# T08-TxClicker-Rev1a.net
KiCad netlist of a schematic drawn in EAGLE
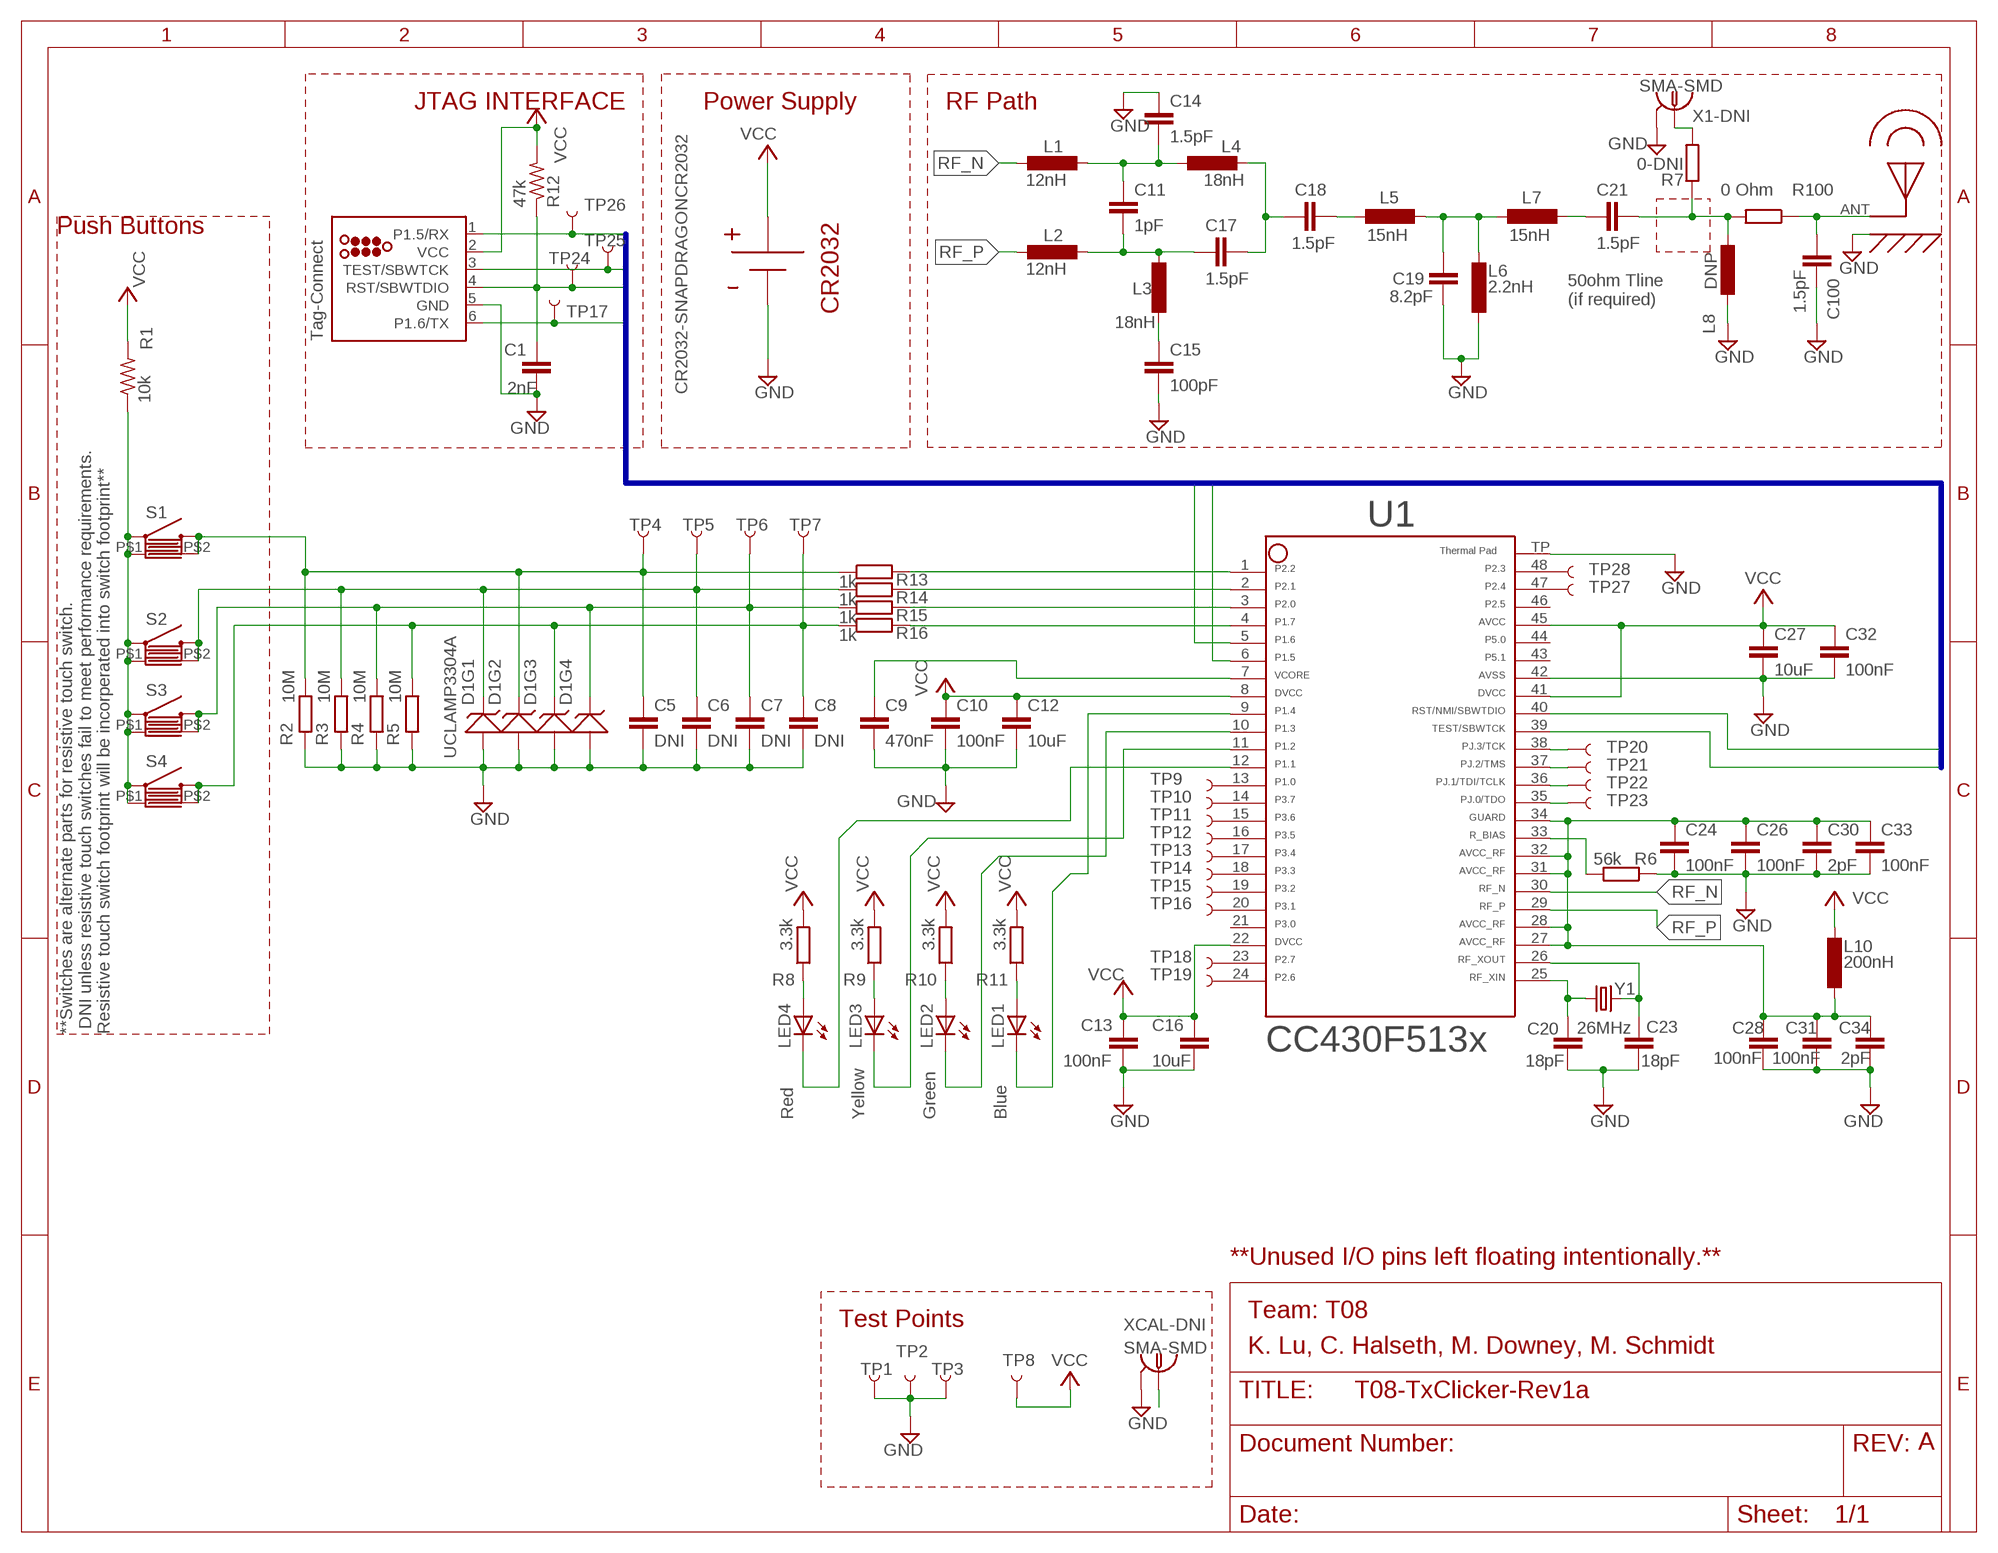
[diagram p0: schematic, sheet 1]

(export (version "E")
  (design (tool "Eeschema 10.0.6"))
  (components
    (comp (ref "C1")
      (value "2nF")
      (footprint "eagle-import:C0603")
      (libsource (lib "eagle-import") (part "C0603"))
    )
    (comp (ref "C5")
      (value "DNI")
      (footprint "eagle-import:C0603")
      (libsource (lib "eagle-import") (part "C0603"))
    )
    (comp (ref "C6")
      (value "DNI")
      (footprint "eagle-import:C0603")
      (libsource (lib "eagle-import") (part "C0603"))
    )
    (comp (ref "C7")
      (value "DNI")
      (footprint "eagle-import:C0603")
      (libsource (lib "eagle-import") (part "C0603"))
    )
    (comp (ref "C8")
      (value "DNI")
      (footprint "eagle-import:C0603")
      (libsource (lib "eagle-import") (part "C0603"))
    )
    (comp (ref "C9")
      (value "470nF")
      (footprint "eagle-import:C0603")
      (libsource (lib "eagle-import") (part "C0603"))
    )
    (comp (ref "C10")
      (value "100nF")
      (footprint "eagle-import:C0603")
      (libsource (lib "eagle-import") (part "C0603"))
    )
    (comp (ref "C11")
      (value "1pF")
      (footprint "eagle-import:C0402")
      (libsource (lib "eagle-import") (part "C0402"))
    )
    (comp (ref "C12")
      (value "10uF")
      (footprint "eagle-import:C0603")
      (libsource (lib "eagle-import") (part "C0603"))
    )
    (comp (ref "C13")
      (value "100nF")
      (footprint "eagle-import:C0603")
      (libsource (lib "eagle-import") (part "C0603"))
    )
    (comp (ref "C14")
      (value "1.5pF")
      (footprint "eagle-import:C0402")
      (libsource (lib "eagle-import") (part "C0402"))
    )
    (comp (ref "C15")
      (value "100pF")
      (footprint "eagle-import:C0402")
      (libsource (lib "eagle-import") (part "C0402"))
    )
    (comp (ref "C16")
      (value "10uF")
      (footprint "eagle-import:C0603")
      (libsource (lib "eagle-import") (part "C0603"))
    )
    (comp (ref "C17")
      (value "1.5pF")
      (footprint "eagle-import:C0402")
      (libsource (lib "eagle-import") (part "C0402"))
    )
    (comp (ref "C18")
      (value "1.5pF")
      (footprint "eagle-import:C0402")
      (libsource (lib "eagle-import") (part "C0402"))
    )
    (comp (ref "C19")
      (value "8.2pF")
      (footprint "eagle-import:C0402")
      (libsource (lib "eagle-import") (part "C0402"))
    )
    (comp (ref "C20")
      (value "18pF")
      (footprint "eagle-import:C0603")
      (libsource (lib "eagle-import") (part "C0603"))
    )
    (comp (ref "C21")
      (value "1.5pF")
      (footprint "eagle-import:C0402")
      (libsource (lib "eagle-import") (part "C0402"))
    )
    (comp (ref "C23")
      (value "18pF")
      (footprint "eagle-import:C0603")
      (libsource (lib "eagle-import") (part "C0603"))
    )
    (comp (ref "C24")
      (value "100nF")
      (footprint "eagle-import:C0603")
      (libsource (lib "eagle-import") (part "C0603"))
    )
    (comp (ref "C26")
      (value "100nF")
      (footprint "eagle-import:C0603")
      (libsource (lib "eagle-import") (part "C0603"))
    )
    (comp (ref "C27")
      (value "10uF")
      (footprint "eagle-import:C0603")
      (libsource (lib "eagle-import") (part "C0603"))
    )
    (comp (ref "C28")
      (value "100nF")
      (footprint "eagle-import:C0603")
      (libsource (lib "eagle-import") (part "C0603"))
    )
    (comp (ref "C30")
      (value "2pF")
      (footprint "eagle-import:C0603")
      (libsource (lib "eagle-import") (part "C0603"))
    )
    (comp (ref "C31")
      (value "100nF")
      (footprint "eagle-import:C0603")
      (libsource (lib "eagle-import") (part "C0603"))
    )
    (comp (ref "C32")
      (value "100nF")
      (footprint "eagle-import:C0603")
      (libsource (lib "eagle-import") (part "C0603"))
    )
    (comp (ref "C33")
      (value "100nF")
      (footprint "eagle-import:C0603")
      (libsource (lib "eagle-import") (part "C0603"))
    )
    (comp (ref "C34")
      (value "2pF")
      (footprint "eagle-import:C0603")
      (libsource (lib "eagle-import") (part "C0603"))
    )
    (comp (ref "C100")
      (value "1.5pF")
      (footprint "eagle-import:C0402")
      (libsource (lib "eagle-import") (part "C0402"))
    )
    (comp (ref "D1")
      (value "UCLAMP3304A")
      (footprint "eagle-import:SOT666")
      (libsource (lib "eagle-import") (part "UCLAMP3304A"))
    )
    (comp (ref "L1")
      (value "12nH")
      (footprint "eagle-import:L0402")
      (libsource (lib "eagle-import") (part "LL0402"))
    )
    (comp (ref "L2")
      (value "12nH")
      (footprint "eagle-import:L0402")
      (libsource (lib "eagle-import") (part "LL0402"))
    )
    (comp (ref "L3")
      (value "18nH")
      (footprint "eagle-import:L0402")
      (libsource (lib "eagle-import") (part "LL0402"))
    )
    (comp (ref "L4")
      (value "18nH")
      (footprint "eagle-import:L0402")
      (libsource (lib "eagle-import") (part "LL0402"))
    )
    (comp (ref "L5")
      (value "15nH")
      (footprint "eagle-import:L0402")
      (libsource (lib "eagle-import") (part "LL0402"))
    )
    (comp (ref "L6")
      (value "2.2nH")
      (footprint "eagle-import:L0402")
      (libsource (lib "eagle-import") (part "LL0402"))
    )
    (comp (ref "L7")
      (value "15nH")
      (footprint "eagle-import:L0402")
      (libsource (lib "eagle-import") (part "LL0402"))
    )
    (comp (ref "L8")
      (value "DNP")
      (footprint "eagle-import:L0402")
      (libsource (lib "eagle-import") (part "LL0402"))
    )
    (comp (ref "L10")
      (value "200nH")
      (footprint "eagle-import:L0603")
      (libsource (lib "eagle-import") (part "LL0603"))
    )
    (comp (ref "LED1")
      (value "Blue")
      (footprint "eagle-import:CHIP-LED0603")
      (libsource (lib "eagle-import") (part "LEDCHIP-LED0603"))
    )
    (comp (ref "LED2")
      (value "Green")
      (footprint "eagle-import:CHIP-LED0603")
      (libsource (lib "eagle-import") (part "LEDCHIP-LED0603"))
    )
    (comp (ref "LED3")
      (value "Yellow")
      (footprint "eagle-import:CHIP-LED0603")
      (libsource (lib "eagle-import") (part "LEDCHIP-LED0603"))
    )
    (comp (ref "LED4")
      (value "Red")
      (footprint "eagle-import:CHIP-LED0603")
      (libsource (lib "eagle-import") (part "LEDCHIP-LED0603"))
    )
    (comp (ref "R1")
      (value "10k")
      (footprint "eagle-import:R0603")
      (libsource (lib "eagle-import") (part "R-US_R0603"))
    )
    (comp (ref "R2")
      (value "10M")
      (footprint "eagle-import:R0603")
      (libsource (lib "eagle-import") (part "R0603"))
    )
    (comp (ref "R3")
      (value "10M")
      (footprint "eagle-import:R0603")
      (libsource (lib "eagle-import") (part "R0603"))
    )
    (comp (ref "R4")
      (value "10M")
      (footprint "eagle-import:R0603")
      (libsource (lib "eagle-import") (part "R0603"))
    )
    (comp (ref "R5")
      (value "10M")
      (footprint "eagle-import:R0603")
      (libsource (lib "eagle-import") (part "R0603"))
    )
    (comp (ref "R6")
      (value "56k")
      (footprint "eagle-import:R0603")
      (libsource (lib "eagle-import") (part "R0603"))
    )
    (comp (ref "R7")
      (value "0-DNI")
      (footprint "eagle-import:R0603")
      (libsource (lib "eagle-import") (part "R0603"))
    )
    (comp (ref "R8")
      (value "3.3k")
      (footprint "eagle-import:R0603")
      (libsource (lib "eagle-import") (part "R0603"))
    )
    (comp (ref "R9")
      (value "3.3k")
      (footprint "eagle-import:R0603")
      (libsource (lib "eagle-import") (part "R0603"))
    )
    (comp (ref "R10")
      (value "3.3k")
      (footprint "eagle-import:R0603")
      (libsource (lib "eagle-import") (part "R0603"))
    )
    (comp (ref "R11")
      (value "3.3k")
      (footprint "eagle-import:R0603")
      (libsource (lib "eagle-import") (part "R0603"))
    )
    (comp (ref "R12")
      (value "47k")
      (footprint "eagle-import:R0603")
      (libsource (lib "eagle-import") (part "R-US_R0603"))
    )
    (comp (ref "R13")
      (value "1k")
      (footprint "eagle-import:R0603")
      (libsource (lib "eagle-import") (part "R0603"))
    )
    (comp (ref "R14")
      (value "1k")
      (footprint "eagle-import:R0603")
      (libsource (lib "eagle-import") (part "R0603"))
    )
    (comp (ref "R15")
      (value "1k")
      (footprint "eagle-import:R0603")
      (libsource (lib "eagle-import") (part "R0603"))
    )
    (comp (ref "R16")
      (value "1k")
      (footprint "eagle-import:R0603")
      (libsource (lib "eagle-import") (part "R0603"))
    )
    (comp (ref "R100")
      (value "0 Ohm")
      (footprint "eagle-import:R0402")
      (libsource (lib "eagle-import") (part "R0402"))
    )
    (comp (ref "S1")
      (value "TOUCHPAD_SWITCH_COMBOSWITC_TOUCHPAD")
      (footprint "eagle-import:TACTILE-PTH-12MM")
      (libsource (lib "eagle-import") (part "TOUCHPAD_SWITCH_COMBOSWITC_TOUCHPAD"))
    )
    (comp (ref "S2")
      (value "TOUCHPAD_SWITCH_COMBOSWITC_TOUCHPAD")
      (footprint "eagle-import:TACTILE-PTH-12MM")
      (libsource (lib "eagle-import") (part "TOUCHPAD_SWITCH_COMBOSWITC_TOUCHPAD"))
    )
    (comp (ref "S3")
      (value "TOUCHPAD_SWITCH_COMBOSWITC_TOUCHPAD")
      (footprint "eagle-import:TACTILE-PTH-12MM")
      (libsource (lib "eagle-import") (part "TOUCHPAD_SWITCH_COMBOSWITC_TOUCHPAD"))
    )
    (comp (ref "S4")
      (value "TOUCHPAD_SWITCH_COMBOSWITC_TOUCHPAD")
      (footprint "eagle-import:TACTILE-PTH-12MM")
      (libsource (lib "eagle-import") (part "TOUCHPAD_SWITCH_COMBOSWITC_TOUCHPAD"))
    )
    (comp (ref "TP1")
      (value "TEST-POINT3")
      (footprint "eagle-import:PAD.03X.03")
      (libsource (lib "eagle-import") (part "TEST-POINT3"))
    )
    (comp (ref "TP2")
      (value "TEST-POINT3")
      (footprint "eagle-import:PAD.03X.03")
      (libsource (lib "eagle-import") (part "TEST-POINT3"))
    )
    (comp (ref "TP3")
      (value "TEST-POINT3")
      (footprint "eagle-import:PAD.03X.03")
      (libsource (lib "eagle-import") (part "TEST-POINT3"))
    )
    (comp (ref "TP4")
      (value "TEST-POINT3")
      (footprint "eagle-import:PAD.03X.03")
      (libsource (lib "eagle-import") (part "TEST-POINT3"))
    )
    (comp (ref "TP5")
      (value "TEST-POINT3")
      (footprint "eagle-import:PAD.03X.03")
      (libsource (lib "eagle-import") (part "TEST-POINT3"))
    )
    (comp (ref "TP6")
      (value "TEST-POINT3")
      (footprint "eagle-import:PAD.03X.03")
      (libsource (lib "eagle-import") (part "TEST-POINT3"))
    )
    (comp (ref "TP7")
      (value "TEST-POINT3")
      (footprint "eagle-import:PAD.03X.03")
      (libsource (lib "eagle-import") (part "TEST-POINT3"))
    )
    (comp (ref "TP8")
      (value "TEST-POINT3")
      (footprint "eagle-import:PAD.03X.03")
      (libsource (lib "eagle-import") (part "TEST-POINT3"))
    )
    (comp (ref "TP9")
      (value "TP9")
      (footprint "eagle-import:PAD.03X.03")
      (libsource (lib "eagle-import") (part "TEST-POINT3"))
    )
    (comp (ref "TP10")
      (value "TEST-POINT3")
      (footprint "eagle-import:PAD.03X.03")
      (libsource (lib "eagle-import") (part "TEST-POINT3"))
    )
    (comp (ref "TP11")
      (value "TEST-POINT3")
      (footprint "eagle-import:PAD.03X.03")
      (libsource (lib "eagle-import") (part "TEST-POINT3"))
    )
    (comp (ref "TP12")
      (value "TEST-POINT3")
      (footprint "eagle-import:PAD.03X.03")
      (libsource (lib "eagle-import") (part "TEST-POINT3"))
    )
    (comp (ref "TP13")
      (value "TEST-POINT3")
      (footprint "eagle-import:PAD.03X.03")
      (libsource (lib "eagle-import") (part "TEST-POINT3"))
    )
    (comp (ref "TP14")
      (value "TEST-POINT3")
      (footprint "eagle-import:PAD.03X.03")
      (libsource (lib "eagle-import") (part "TEST-POINT3"))
    )
    (comp (ref "TP15")
      (value "TEST-POINT3")
      (footprint "eagle-import:PAD.03X.03")
      (libsource (lib "eagle-import") (part "TEST-POINT3"))
    )
    (comp (ref "TP16")
      (value "TEST-POINT3")
      (footprint "eagle-import:PAD.03X.03")
      (libsource (lib "eagle-import") (part "TEST-POINT3"))
    )
    (comp (ref "TP17")
      (value "TEST-POINT3")
      (footprint "eagle-import:PAD.03X.03")
      (libsource (lib "eagle-import") (part "TEST-POINT3"))
    )
    (comp (ref "TP18")
      (value "TEST-POINT3")
      (footprint "eagle-import:PAD.03X.03")
      (libsource (lib "eagle-import") (part "TEST-POINT3"))
    )
    (comp (ref "TP19")
      (value "TEST-POINT3")
      (footprint "eagle-import:PAD.03X.03")
      (libsource (lib "eagle-import") (part "TEST-POINT3"))
    )
    (comp (ref "TP20")
      (value "TEST-POINT3")
      (footprint "eagle-import:PAD.03X.03")
      (libsource (lib "eagle-import") (part "TEST-POINT3"))
    )
    (comp (ref "TP21")
      (value "TEST-POINT3")
      (footprint "eagle-import:PAD.03X.03")
      (libsource (lib "eagle-import") (part "TEST-POINT3"))
    )
    (comp (ref "TP22")
      (value "TEST-POINT3")
      (footprint "eagle-import:PAD.03X.03")
      (libsource (lib "eagle-import") (part "TEST-POINT3"))
    )
    (comp (ref "TP23")
      (value "TEST-POINT3")
      (footprint "eagle-import:PAD.03X.03")
      (libsource (lib "eagle-import") (part "TEST-POINT3"))
    )
    (comp (ref "TP24")
      (value "TEST-POINT3")
      (footprint "eagle-import:PAD.03X.03")
      (libsource (lib "eagle-import") (part "TEST-POINT3"))
    )
    (comp (ref "TP25")
      (value "TEST-POINT3")
      (footprint "eagle-import:PAD.03X.03")
      (libsource (lib "eagle-import") (part "TEST-POINT3"))
    )
    (comp (ref "TP26")
      (value "TEST-POINT3")
      (footprint "eagle-import:PAD.03X.03")
      (libsource (lib "eagle-import") (part "TEST-POINT3"))
    )
    (comp (ref "TP27")
      (value "TEST-POINT3")
      (footprint "eagle-import:PAD.03X.03")
      (libsource (lib "eagle-import") (part "TEST-POINT3"))
    )
    (comp (ref "TP28")
      (value "TEST-POINT3")
      (footprint "eagle-import:PAD.03X.03")
      (libsource (lib "eagle-import") (part "TEST-POINT3"))
    )
    (comp (ref "U$1")
      (value "TC2030-MCP")
      (footprint "eagle-import:TC2030-MCP")
      (libsource (lib "eagle-import") (part "TC2030-MCP"))
    )
    (comp (ref "U$5")
      (value "CR2032-SNAPDRAGONCR2032")
      (footprint "eagle-import:CR2032-SNAPDRAGON")
      (libsource (lib "eagle-import") (part "CR2032-SNAPDRAGONCR2032"))
    )
    (comp (ref "U$6")
      (value "PCB_ANTENNA_915MHZOSHP")
      (footprint "eagle-import:PCB_ANTENNA_915MHZ")
      (libsource (lib "eagle-import") (part "PCB_ANTENNA_915MHZOSHP"))
    )
    (comp (ref "U1")
      (value "CC430F513X---RGZ48")
      (footprint "eagle-import:RGZ48")
      (libsource (lib "eagle-import") (part "CC430F513X---RGZ48"))
    )
    (comp (ref "X1-DNI")
      (value "SMA-SMD")
      (footprint "eagle-import:SMA-SMD")
      (libsource (lib "eagle-import") (part "SMA-SMD"))
    )
    (comp (ref "XCAL-DNI")
      (value "SMA-SMD")
      (footprint "eagle-import:SMA-SMD")
      (libsource (lib "eagle-import") (part "SMA-SMD"))
    )
    (comp (ref "Y1")
      (value "26MHz")
      (footprint "eagle-import:CRYSTAL-TXC-7A")
      (libsource (lib "eagle-import") (part "CRYSTALTXC-7A"))
    )
  )
  (nets
    (net (code "1") (name "/P1.5{slash}RX") (class "Default")
      (node (ref "TP26") (pin "P$1") (pinfunction "1_P$1") (pintype "bidirectional"))
      (node (ref "U$1") (pin "1") (pinfunction "P1.5/RX_1") (pintype "bidirectional"))
      (node (ref "U1") (pin "6") (pinfunction "6_6") (pintype "bidirectional"))
    )
    (net (code "2") (name "/P1.6{slash}TX") (class "Default")
      (node (ref "TP17") (pin "P$1") (pinfunction "1_P$1") (pintype "bidirectional"))
      (node (ref "U$1") (pin "6") (pinfunction "P1.6/TX_6") (pintype "bidirectional"))
      (node (ref "U1") (pin "5") (pinfunction "5_5") (pintype "bidirectional"))
    )
    (net (code "3") (name "/RST{slash}NMI{slash}SBWTDIO") (class "Default")
      (node (ref "C1") (pin "1") (pinfunction "1_1") (pintype "passive"))
      (node (ref "R12") (pin "1") (pinfunction "1_1") (pintype "passive"))
      (node (ref "TP24") (pin "P$1") (pinfunction "1_P$1") (pintype "bidirectional"))
      (node (ref "U$1") (pin "4") (pinfunction "RST/SBWTDIO_4") (pintype "bidirectional"))
      (node (ref "U1") (pin "40") (pinfunction "40_40") (pintype "bidirectional"))
    )
    (net (code "4") (name "/TEST{slash}SBWTCK") (class "Default")
      (node (ref "TP25") (pin "P$1") (pinfunction "1_P$1") (pintype "bidirectional"))
      (node (ref "U$1") (pin "3") (pinfunction "TEST/SBWTCK_3") (pintype "bidirectional"))
      (node (ref "U1") (pin "39") (pinfunction "39_39") (pintype "input"))
    )
    (net (code "5") (name "GND") (class "Default")
      (node (ref "C1") (pin "2") (pinfunction "2_2") (pintype "passive"))
      (node (ref "C10") (pin "2") (pinfunction "2_2") (pintype "passive"))
      (node (ref "C100") (pin "P$1") (pinfunction "1_P$1") (pintype "passive"))
      (node (ref "C12") (pin "2") (pinfunction "2_2") (pintype "passive"))
      (node (ref "C13") (pin "2") (pinfunction "2_2") (pintype "passive"))
      (node (ref "C14") (pin "P$1") (pinfunction "1_P$1") (pintype "passive"))
      (node (ref "C15") (pin "P$2") (pinfunction "2_P$2") (pintype "passive"))
      (node (ref "C16") (pin "2") (pinfunction "2_2") (pintype "passive"))
      (node (ref "C19") (pin "P$1") (pinfunction "1_P$1") (pintype "passive"))
      (node (ref "C20") (pin "2") (pinfunction "2_2") (pintype "passive"))
      (node (ref "C23") (pin "2") (pinfunction "2_2") (pintype "passive"))
      (node (ref "C24") (pin "2") (pinfunction "2_2") (pintype "passive"))
      (node (ref "C26") (pin "2") (pinfunction "2_2") (pintype "passive"))
      (node (ref "C27") (pin "2") (pinfunction "2_2") (pintype "passive"))
      (node (ref "C28") (pin "2") (pinfunction "2_2") (pintype "passive"))
      (node (ref "C30") (pin "2") (pinfunction "2_2") (pintype "passive"))
      (node (ref "C31") (pin "2") (pinfunction "2_2") (pintype "passive"))
      (node (ref "C32") (pin "2") (pinfunction "2_2") (pintype "passive"))
      (node (ref "C33") (pin "2") (pinfunction "2_2") (pintype "passive"))
      (node (ref "C34") (pin "2") (pinfunction "2_2") (pintype "passive"))
      (node (ref "C5") (pin "2") (pinfunction "2_2") (pintype "passive"))
      (node (ref "C6") (pin "2") (pinfunction "2_2") (pintype "passive"))
      (node (ref "C7") (pin "2") (pinfunction "2_2") (pintype "passive"))
      (node (ref "C8") (pin "2") (pinfunction "2_2") (pintype "passive"))
      (node (ref "C9") (pin "2") (pinfunction "2_2") (pintype "passive"))
      (node (ref "D1") (pin "2") (pinfunction "2_2") (pintype "bidirectional"))
      (node (ref "D1") (pin "5") (pinfunction "2_5") (pintype "bidirectional"))
      (node (ref "L6") (pin "P$2") (pinfunction "2_P$2") (pintype "passive"))
      (node (ref "L8") (pin "P$1") (pinfunction "1_P$1") (pintype "passive"))
      (node (ref "R2") (pin "1") (pinfunction "1_1") (pintype "passive"))
      (node (ref "R3") (pin "1") (pinfunction "1_1") (pintype "passive"))
      (node (ref "R4") (pin "1") (pinfunction "1_1") (pintype "passive"))
      (node (ref "R5") (pin "1") (pinfunction "1_1") (pintype "passive"))
      (node (ref "R6") (pin "1") (pinfunction "1_1") (pintype "passive"))
      (node (ref "TP1") (pin "P$1") (pinfunction "1_P$1") (pintype "bidirectional"))
      (node (ref "TP2") (pin "P$1") (pinfunction "1_P$1") (pintype "bidirectional"))
      (node (ref "TP3") (pin "P$1") (pinfunction "1_P$1") (pintype "bidirectional"))
      (node (ref "U$1") (pin "5") (pinfunction "GND_5") (pintype "power_in"))
      (node (ref "U$5") (pin "V-") (pinfunction "V-_V-") (pintype "bidirectional"))
      (node (ref "U$6") (pin "GPLANE") (pinfunction "GND_GPLANE") (pintype "power_in"))
      (node (ref "U1") (pin "42") (pinfunction "42_42") (pintype "power_in"))
      (node (ref "U1") (pin "TP") (pinfunction "49_TP") (pintype "power_in"))
      (node (ref "X1-DNI") (pin "2@1") (pinfunction "2_2@1") (pintype "passive"))
      (node (ref "X1-DNI") (pin "2@2") (pinfunction "2_2@2") (pintype "passive"))
      (node (ref "X1-DNI") (pin "2@3") (pinfunction "2_2@3") (pintype "passive"))
      (node (ref "X1-DNI") (pin "2@4") (pinfunction "2_2@4") (pintype "passive"))
      (node (ref "X1-DNI") (pin "2@5") (pinfunction "2_2@5") (pintype "passive"))
      (node (ref "X1-DNI") (pin "2@6") (pinfunction "2_2@6") (pintype "passive"))
      (node (ref "XCAL-DNI") (pin "2@1") (pinfunction "2_2@1") (pintype "passive"))
      (node (ref "XCAL-DNI") (pin "2@2") (pinfunction "2_2@2") (pintype "passive"))
      (node (ref "XCAL-DNI") (pin "2@3") (pinfunction "2_2@3") (pintype "passive"))
      (node (ref "XCAL-DNI") (pin "2@4") (pinfunction "2_2@4") (pintype "passive"))
      (node (ref "XCAL-DNI") (pin "2@5") (pinfunction "2_2@5") (pintype "passive"))
      (node (ref "XCAL-DNI") (pin "2@6") (pinfunction "2_2@6") (pintype "passive"))
    )
    (net (code "6") (name "Net-(C9-Pad1)") (class "Default")
      (node (ref "C9") (pin "1") (pinfunction "1_1") (pintype "passive"))
      (node (ref "U1") (pin "7") (pinfunction "7_7") (pintype "power_in"))
    )
    (net (code "7") (name "Net-(C11-1)") (class "Default")
      (node (ref "C11") (pin "P$1") (pinfunction "1_P$1") (pintype "passive"))
      (node (ref "C14") (pin "P$2") (pinfunction "2_P$2") (pintype "passive"))
      (node (ref "L1") (pin "P$1") (pinfunction "1_P$1") (pintype "passive"))
      (node (ref "L4") (pin "P$2") (pinfunction "2_P$2") (pintype "passive"))
    )
    (net (code "8") (name "Net-(C11-2)") (class "Default")
      (node (ref "C11") (pin "P$2") (pinfunction "2_P$2") (pintype "passive"))
      (node (ref "C17") (pin "P$2") (pinfunction "2_P$2") (pintype "passive"))
      (node (ref "L2") (pin "P$1") (pinfunction "1_P$1") (pintype "passive"))
      (node (ref "L3") (pin "P$1") (pinfunction "1_P$1") (pintype "passive"))
    )
    (net (code "9") (name "Net-(C15-1)") (class "Default")
      (node (ref "C15") (pin "P$1") (pinfunction "1_P$1") (pintype "passive"))
      (node (ref "L3") (pin "P$2") (pinfunction "2_P$2") (pintype "passive"))
    )
    (net (code "10") (name "Net-(C17-1)") (class "Default")
      (node (ref "C17") (pin "P$1") (pinfunction "1_P$1") (pintype "passive"))
      (node (ref "C18") (pin "P$1") (pinfunction "1_P$1") (pintype "passive"))
      (node (ref "L4") (pin "P$1") (pinfunction "1_P$1") (pintype "passive"))
    )
    (net (code "11") (name "Net-(C18-2)") (class "Default")
      (node (ref "C18") (pin "P$2") (pinfunction "2_P$2") (pintype "passive"))
      (node (ref "L5") (pin "P$1") (pinfunction "1_P$1") (pintype "passive"))
    )
    (net (code "12") (name "Net-(C19-2)") (class "Default")
      (node (ref "C19") (pin "P$2") (pinfunction "2_P$2") (pintype "passive"))
      (node (ref "L5") (pin "P$2") (pinfunction "2_P$2") (pintype "passive"))
      (node (ref "L6") (pin "P$1") (pinfunction "1_P$1") (pintype "passive"))
      (node (ref "L7") (pin "P$1") (pinfunction "1_P$1") (pintype "passive"))
    )
    (net (code "13") (name "Net-(C21-1)") (class "Default")
      (node (ref "C21") (pin "P$1") (pinfunction "1_P$1") (pintype "passive"))
      (node (ref "L8") (pin "P$2") (pinfunction "2_P$2") (pintype "passive"))
      (node (ref "R100") (pin "P$2") (pinfunction "2_P$2") (pintype "passive"))
      (node (ref "R7") (pin "1") (pinfunction "1_1") (pintype "passive"))
    )
    (net (code "14") (name "Net-(C21-2)") (class "Default")
      (node (ref "C21") (pin "P$2") (pinfunction "2_P$2") (pintype "passive"))
      (node (ref "L7") (pin "P$2") (pinfunction "2_P$2") (pintype "passive"))
    )
    (net (code "15") (name "Net-(C24-Pad1)") (class "Default")
      (node (ref "C24") (pin "1") (pinfunction "1_1") (pintype "passive"))
      (node (ref "C26") (pin "1") (pinfunction "1_1") (pintype "passive"))
      (node (ref "C28") (pin "1") (pinfunction "1_1") (pintype "passive"))
      (node (ref "C30") (pin "1") (pinfunction "1_1") (pintype "passive"))
      (node (ref "C31") (pin "1") (pinfunction "1_1") (pintype "passive"))
      (node (ref "C33") (pin "1") (pinfunction "1_1") (pintype "passive"))
      (node (ref "C34") (pin "1") (pinfunction "1_1") (pintype "passive"))
      (node (ref "L10") (pin "2") (pinfunction "2_2") (pintype "passive"))
      (node (ref "U1") (pin "27") (pinfunction "27_27") (pintype "power_in"))
      (node (ref "U1") (pin "28") (pinfunction "28_28") (pintype "bidirectional"))
      (node (ref "U1") (pin "31") (pinfunction "31_31") (pintype "power_in"))
      (node (ref "U1") (pin "32") (pinfunction "32_32") (pintype "power_in"))
      (node (ref "U1") (pin "34") (pinfunction "34_34") (pintype "power_in"))
    )
    (net (code "16") (name "Net-(C100-2)") (class "Default")
      (node (ref "C100") (pin "P$2") (pinfunction "2_P$2") (pintype "passive"))
      (node (ref "R100") (pin "P$1") (pinfunction "1_P$1") (pintype "passive"))
      (node (ref "U$6") (pin "ANT") (pinfunction "ANT_ANT") (pintype "input"))
    )
    (net (code "17") (name "Net-(D1B-1)") (class "Default")
      (node (ref "C5") (pin "1") (pinfunction "1_1") (pintype "passive"))
      (node (ref "D1") (pin "3") (pinfunction "1_3") (pintype "bidirectional"))
      (node (ref "R13") (pin "1") (pinfunction "1_1") (pintype "passive"))
      (node (ref "R2") (pin "2") (pinfunction "2_2") (pintype "passive"))
      (node (ref "S1") (pin "3") (pinfunction "TOP_3") (pintype "passive"))
      (node (ref "S1") (pin "P$2") (pinfunction "TOP_P$2") (pintype "passive"))
      (node (ref "TP4") (pin "P$1") (pinfunction "1_P$1") (pintype "bidirectional"))
    )
    (net (code "18") (name "Net-(D1C-P$1)") (class "Default")
      (node (ref "C8") (pin "1") (pinfunction "1_1") (pintype "passive"))
      (node (ref "D1") (pin "4") (pinfunction "P$1_4") (pintype "bidirectional"))
      (node (ref "R16") (pin "1") (pinfunction "1_1") (pintype "passive"))
      (node (ref "R5") (pin "2") (pinfunction "2_2") (pintype "passive"))
      (node (ref "S4") (pin "3") (pinfunction "TOP_3") (pintype "passive"))
      (node (ref "S4") (pin "P$2") (pinfunction "TOP_P$2") (pintype "passive"))
      (node (ref "TP7") (pin "P$1") (pinfunction "1_P$1") (pintype "bidirectional"))
    )
    (net (code "19") (name "Net-(D1D-P$1)") (class "Default")
      (node (ref "C7") (pin "1") (pinfunction "1_1") (pintype "passive"))
      (node (ref "D1") (pin "6") (pinfunction "P$1_6") (pintype "bidirectional"))
      (node (ref "R15") (pin "1") (pinfunction "1_1") (pintype "passive"))
      (node (ref "R4") (pin "2") (pinfunction "2_2") (pintype "passive"))
      (node (ref "S3") (pin "3") (pinfunction "TOP_3") (pintype "passive"))
      (node (ref "S3") (pin "P$2") (pinfunction "TOP_P$2") (pintype "passive"))
      (node (ref "TP6") (pin "P$1") (pinfunction "1_P$1") (pintype "bidirectional"))
    )
    (net (code "20") (name "Net-(LED1-PadA)") (class "Default")
      (node (ref "LED1") (pin "A") (pinfunction "A_A") (pintype "bidirectional"))
      (node (ref "R11") (pin "1") (pinfunction "1_1") (pintype "passive"))
    )
    (net (code "21") (name "Net-(LED1-PadC)") (class "Default")
      (node (ref "LED1") (pin "C") (pinfunction "C_C") (pintype "bidirectional"))
      (node (ref "U1") (pin "9") (pinfunction "9_9") (pintype "bidirectional"))
    )
    (net (code "22") (name "Net-(LED2-PadA)") (class "Default")
      (node (ref "LED2") (pin "A") (pinfunction "A_A") (pintype "bidirectional"))
      (node (ref "R10") (pin "1") (pinfunction "1_1") (pintype "passive"))
    )
    (net (code "23") (name "Net-(LED2-PadC)") (class "Default")
      (node (ref "LED2") (pin "C") (pinfunction "C_C") (pintype "bidirectional"))
      (node (ref "U1") (pin "10") (pinfunction "10_10") (pintype "bidirectional"))
    )
    (net (code "24") (name "Net-(LED3-PadA)") (class "Default")
      (node (ref "LED3") (pin "A") (pinfunction "A_A") (pintype "bidirectional"))
      (node (ref "R9") (pin "1") (pinfunction "1_1") (pintype "passive"))
    )
    (net (code "25") (name "Net-(LED3-PadC)") (class "Default")
      (node (ref "LED3") (pin "C") (pinfunction "C_C") (pintype "bidirectional"))
      (node (ref "U1") (pin "11") (pinfunction "11_11") (pintype "bidirectional"))
    )
    (net (code "26") (name "Net-(LED4-PadA)") (class "Default")
      (node (ref "LED4") (pin "A") (pinfunction "A_A") (pintype "bidirectional"))
      (node (ref "R8") (pin "1") (pinfunction "1_1") (pintype "passive"))
    )
    (net (code "27") (name "Net-(LED4-PadC)") (class "Default")
      (node (ref "LED4") (pin "C") (pinfunction "C_C") (pintype "bidirectional"))
      (node (ref "U1") (pin "12") (pinfunction "12_12") (pintype "bidirectional"))
    )
    (net (code "28") (name "Net-(R1-Pad1)") (class "Default")
      (node (ref "R1") (pin "1") (pinfunction "1_1") (pintype "passive"))
      (node (ref "S1") (pin "1") (pinfunction "BASE_1") (pintype "passive"))
      (node (ref "S1") (pin "P$1") (pinfunction "BASE_P$1") (pintype "passive"))
      (node (ref "S2") (pin "1") (pinfunction "BASE_1") (pintype "passive"))
      (node (ref "S2") (pin "P$1") (pinfunction "BASE_P$1") (pintype "passive"))
      (node (ref "S3") (pin "1") (pinfunction "BASE_1") (pintype "passive"))
      (node (ref "S3") (pin "P$1") (pinfunction "BASE_P$1") (pintype "passive"))
      (node (ref "S4") (pin "1") (pinfunction "BASE_1") (pintype "passive"))
      (node (ref "S4") (pin "P$1") (pinfunction "BASE_P$1") (pintype "passive"))
    )
    (net (code "29") (name "Net-(R6-Pad2)") (class "Default")
      (node (ref "R6") (pin "2") (pinfunction "2_2") (pintype "passive"))
      (node (ref "U1") (pin "33") (pinfunction "33_33") (pintype "power_in"))
    )
    (net (code "30") (name "Net-(R7-Pad2)") (class "Default")
      (node (ref "R7") (pin "2") (pinfunction "2_2") (pintype "passive"))
      (node (ref "X1-DNI") (pin "1") (pinfunction "1_1") (pintype "passive"))
    )
    (net (code "31") (name "Net-(R13-Pad2)") (class "Default")
      (node (ref "R13") (pin "2") (pinfunction "2_2") (pintype "passive"))
      (node (ref "U1") (pin "1") (pinfunction "1_1") (pintype "bidirectional"))
    )
    (net (code "32") (name "Net-(R14-Pad2)") (class "Default")
      (node (ref "R14") (pin "2") (pinfunction "2_2") (pintype "passive"))
      (node (ref "U1") (pin "2") (pinfunction "2_2") (pintype "bidirectional"))
    )
    (net (code "33") (name "Net-(R15-Pad2)") (class "Default")
      (node (ref "R15") (pin "2") (pinfunction "2_2") (pintype "passive"))
      (node (ref "U1") (pin "3") (pinfunction "3_3") (pintype "bidirectional"))
    )
    (net (code "34") (name "Net-(R16-Pad2)") (class "Default")
      (node (ref "R16") (pin "2") (pinfunction "2_2") (pintype "passive"))
      (node (ref "U1") (pin "4") (pinfunction "4_4") (pintype "bidirectional"))
    )
    (net (code "35") (name "Net-(TP5-1)") (class "Default")
      (node (ref "C6") (pin "1") (pinfunction "1_1") (pintype "passive"))
      (node (ref "D1") (pin "1") (pinfunction "1_1") (pintype "bidirectional"))
      (node (ref "R14") (pin "1") (pinfunction "1_1") (pintype "passive"))
      (node (ref "R3") (pin "2") (pinfunction "2_2") (pintype "passive"))
      (node (ref "S2") (pin "3") (pinfunction "TOP_3") (pintype "passive"))
      (node (ref "S2") (pin "P$2") (pinfunction "TOP_P$2") (pintype "passive"))
      (node (ref "TP5") (pin "P$1") (pinfunction "1_P$1") (pintype "bidirectional"))
    )
    (net (code "36") (name "Net-(TP9-1)") (class "Default")
      (node (ref "TP9") (pin "P$1") (pinfunction "1_P$1") (pintype "bidirectional"))
      (node (ref "U1") (pin "13") (pinfunction "13_13") (pintype "bidirectional"))
    )
    (net (code "37") (name "Net-(TP10-1)") (class "Default")
      (node (ref "TP10") (pin "P$1") (pinfunction "1_P$1") (pintype "bidirectional"))
      (node (ref "U1") (pin "14") (pinfunction "14_14") (pintype "bidirectional"))
    )
    (net (code "38") (name "Net-(TP11-1)") (class "Default")
      (node (ref "TP11") (pin "P$1") (pinfunction "1_P$1") (pintype "bidirectional"))
      (node (ref "U1") (pin "15") (pinfunction "15_15") (pintype "bidirectional"))
    )
    (net (code "39") (name "Net-(TP12-1)") (class "Default")
      (node (ref "TP12") (pin "P$1") (pinfunction "1_P$1") (pintype "bidirectional"))
      (node (ref "U1") (pin "16") (pinfunction "16_16") (pintype "bidirectional"))
    )
    (net (code "40") (name "Net-(TP13-1)") (class "Default")
      (node (ref "TP13") (pin "P$1") (pinfunction "1_P$1") (pintype "bidirectional"))
      (node (ref "U1") (pin "17") (pinfunction "17_17") (pintype "bidirectional"))
    )
    (net (code "41") (name "Net-(TP14-1)") (class "Default")
      (node (ref "TP14") (pin "P$1") (pinfunction "1_P$1") (pintype "bidirectional"))
      (node (ref "U1") (pin "18") (pinfunction "18_18") (pintype "bidirectional"))
    )
    (net (code "42") (name "Net-(TP15-1)") (class "Default")
      (node (ref "TP15") (pin "P$1") (pinfunction "1_P$1") (pintype "bidirectional"))
      (node (ref "U1") (pin "19") (pinfunction "19_19") (pintype "bidirectional"))
    )
    (net (code "43") (name "Net-(TP16-1)") (class "Default")
      (node (ref "TP16") (pin "P$1") (pinfunction "1_P$1") (pintype "bidirectional"))
      (node (ref "U1") (pin "20") (pinfunction "20_20") (pintype "bidirectional"))
    )
    (net (code "44") (name "Net-(TP18-1)") (class "Default")
      (node (ref "TP18") (pin "P$1") (pinfunction "1_P$1") (pintype "bidirectional"))
      (node (ref "U1") (pin "23") (pinfunction "23_23") (pintype "bidirectional"))
    )
    (net (code "45") (name "Net-(TP19-1)") (class "Default")
      (node (ref "TP19") (pin "P$1") (pinfunction "1_P$1") (pintype "bidirectional"))
      (node (ref "U1") (pin "24") (pinfunction "24_24") (pintype "bidirectional"))
    )
    (net (code "46") (name "Net-(TP20-1)") (class "Default")
      (node (ref "TP20") (pin "P$1") (pinfunction "1_P$1") (pintype "bidirectional"))
      (node (ref "U1") (pin "38") (pinfunction "38_38") (pintype "bidirectional"))
    )
    (net (code "47") (name "Net-(TP21-1)") (class "Default")
      (node (ref "TP21") (pin "P$1") (pinfunction "1_P$1") (pintype "bidirectional"))
      (node (ref "U1") (pin "37") (pinfunction "37_37") (pintype "bidirectional"))
    )
    (net (code "48") (name "Net-(TP22-1)") (class "Default")
      (node (ref "TP22") (pin "P$1") (pinfunction "1_P$1") (pintype "bidirectional"))
      (node (ref "U1") (pin "36") (pinfunction "36_36") (pintype "bidirectional"))
    )
    (net (code "49") (name "Net-(TP23-1)") (class "Default")
      (node (ref "TP23") (pin "P$1") (pinfunction "1_P$1") (pintype "bidirectional"))
      (node (ref "U1") (pin "35") (pinfunction "35_35") (pintype "bidirectional"))
    )
    (net (code "50") (name "Net-(TP27-1)") (class "Default")
      (node (ref "TP27") (pin "P$1") (pinfunction "1_P$1") (pintype "bidirectional"))
      (node (ref "U1") (pin "47") (pinfunction "47_47") (pintype "bidirectional"))
    )
    (net (code "51") (name "Net-(TP28-1)") (class "Default")
      (node (ref "TP28") (pin "P$1") (pinfunction "1_P$1") (pintype "bidirectional"))
      (node (ref "U1") (pin "48") (pinfunction "48_48") (pintype "bidirectional"))
    )
    (net (code "52") (name "Net-(Y1-1)") (class "Default")
      (node (ref "C20") (pin "1") (pinfunction "1_1") (pintype "passive"))
      (node (ref "U1") (pin "25") (pinfunction "25_25") (pintype "input"))
      (node (ref "Y1") (pin "P$1") (pinfunction "1_P$1") (pintype "passive"))
    )
    (net (code "53") (name "Net-(Y1-2)") (class "Default")
      (node (ref "C23") (pin "1") (pinfunction "1_1") (pintype "passive"))
      (node (ref "U1") (pin "26") (pinfunction "26_26") (pintype "output"))
      (node (ref "Y1") (pin "P$2") (pinfunction "2_P$2") (pintype "passive"))
    )
    (net (code "54") (name "RF_N") (class "Default")
      (node (ref "L1") (pin "P$2") (pinfunction "2_P$2") (pintype "passive"))
      (node (ref "U1") (pin "30") (pinfunction "30_30") (pintype "bidirectional"))
    )
    (net (code "55") (name "RF_P") (class "Default")
      (node (ref "L2") (pin "P$2") (pinfunction "2_P$2") (pintype "passive"))
      (node (ref "U1") (pin "29") (pinfunction "29_29") (pintype "bidirectional"))
    )
    (net (code "56") (name "VCC") (class "Default")
      (node (ref "C10") (pin "1") (pinfunction "1_1") (pintype "passive"))
      (node (ref "C12") (pin "1") (pinfunction "1_1") (pintype "passive"))
      (node (ref "C13") (pin "1") (pinfunction "1_1") (pintype "passive"))
      (node (ref "C16") (pin "1") (pinfunction "1_1") (pintype "passive"))
      (node (ref "C27") (pin "1") (pinfunction "1_1") (pintype "passive"))
      (node (ref "C32") (pin "1") (pinfunction "1_1") (pintype "passive"))
      (node (ref "L10") (pin "1") (pinfunction "1_1") (pintype "passive"))
      (node (ref "R1") (pin "2") (pinfunction "2_2") (pintype "passive"))
      (node (ref "R10") (pin "2") (pinfunction "2_2") (pintype "passive"))
      (node (ref "R11") (pin "2") (pinfunction "2_2") (pintype "passive"))
      (node (ref "R12") (pin "2") (pinfunction "2_2") (pintype "passive"))
      (node (ref "R8") (pin "2") (pinfunction "2_2") (pintype "passive"))
      (node (ref "R9") (pin "2") (pinfunction "2_2") (pintype "passive"))
      (node (ref "TP8") (pin "P$1") (pinfunction "1_P$1") (pintype "bidirectional"))
      (node (ref "U$1") (pin "2") (pinfunction "VCC_2") (pintype "power_in"))
      (node (ref "U$5") (pin "V+") (pinfunction "V+_V+") (pintype "passive"))
      (node (ref "U1") (pin "22") (pinfunction "22_22") (pintype "power_in"))
      (node (ref "U1") (pin "41") (pinfunction "41_41") (pintype "power_in"))
      (node (ref "U1") (pin "45") (pinfunction "45_45") (pintype "input"))
      (node (ref "U1") (pin "8") (pinfunction "8_8") (pintype "power_in"))
    )
    (net (code "57") (name "unconnected-(U1-Pad21)") (class "Default")
      (node (ref "U1") (pin "21") (pinfunction "21_21") (pintype "bidirectional"))
    )
    (net (code "58") (name "unconnected-(U1-Pad43)") (class "Default")
      (node (ref "U1") (pin "43") (pinfunction "43_43") (pintype "bidirectional"))
    )
    (net (code "59") (name "unconnected-(U1-Pad44)") (class "Default")
      (node (ref "U1") (pin "44") (pinfunction "44_44") (pintype "bidirectional"))
    )
    (net (code "60") (name "unconnected-(U1-Pad46)") (class "Default")
      (node (ref "U1") (pin "46") (pinfunction "46_46") (pintype "bidirectional"))
    )
    (net (code "61") (name "unconnected-(XCAL-DNI-Pad1)") (class "Default")
      (node (ref "XCAL-DNI") (pin "1") (pinfunction "1_1") (pintype "passive"))
    )
  )
)
